# old_IMU.net
KiCad netlist of a schematic drawn in Altium Designer
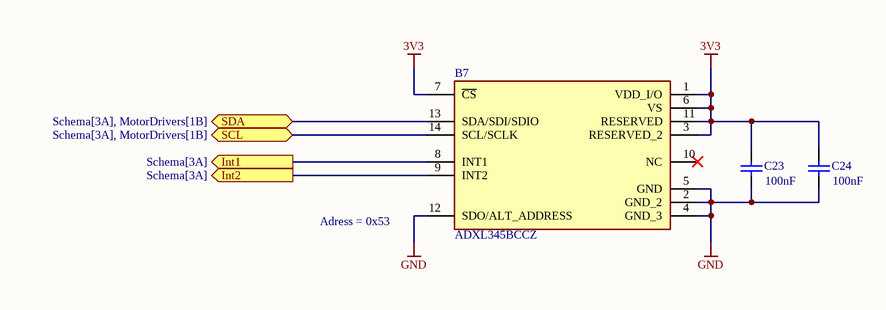
[diagram p0: old_IMU.SchDoc]

(export (version "E")
  (design (tool "Eeschema 10.0.6"))
  (components
    (comp (ref "B7")
      (value "ADXL345BCCZ")
      (footprint "LGA14R80P3X6_300X500X100")
      (description "ADXL345BCCZ, Accelerometer 3-Axis, 0.1  3200 Hz 2  3.6 V, 14-Pin LGA")
      (libsource (lib "SchematicLib") (part "ADXL345BCCZ"))
    )
    (comp (ref "C23")
      (value "100nF")
      (footprint "6-0805_N")
      (description "Capacitor")
      (fields (field (name "Comment") "Cap") (field (name "PUBLISHER") "Altium Limited"))
      (libsource (lib "Miscellaneous Devices") (part "Cap"))
    )
    (comp (ref "C24")
      (value "100nF")
      (footprint "6-0805_N")
      (description "Capacitor")
      (fields (field (name "Comment") "Cap") (field (name "PUBLISHER") "Altium Limited"))
      (libsource (lib "Miscellaneous Devices") (part "Cap"))
    )
  )
  (nets
    (net (code "1") (name "/Int1") (class "Default")
      (node (ref "B7") (pin "8") (pinfunction "INT1_8") (pintype "passive"))
    )
    (net (code "2") (name "/Int2") (class "Default")
      (node (ref "B7") (pin "9") (pinfunction "INT2_9") (pintype "passive"))
    )
    (net (code "3") (name "/SCL") (class "Default")
      (node (ref "B7") (pin "14") (pinfunction "SCL/SCLK_14") (pintype "passive"))
    )
    (net (code "4") (name "/SDA") (class "Default")
      (node (ref "B7") (pin "13") (pinfunction "SDA/SDI/SDIO_13") (pintype "passive"))
    )
    (net (code "5") (name "3V3") (class "Default")
      (node (ref "B7") (pin "1") (pinfunction "VDD_I/O_1") (pintype "passive"))
      (node (ref "B7") (pin "11") (pinfunction "RESERVED_11") (pintype "passive"))
      (node (ref "B7") (pin "3") (pinfunction "RESERVED_2_3") (pintype "passive"))
      (node (ref "B7") (pin "6") (pinfunction "VS_6") (pintype "passive"))
      (node (ref "B7") (pin "7") (pinfunction "~{CS}_7") (pintype "passive"))
      (node (ref "C23") (pin "1") (pinfunction "1_1") (pintype "passive"))
      (node (ref "C24") (pin "1") (pinfunction "1_1") (pintype "passive"))
    )
    (net (code "6") (name "GND") (class "Default")
      (node (ref "B7") (pin "12") (pinfunction "SDO/ALT_ADDRESS_12") (pintype "passive"))
      (node (ref "B7") (pin "2") (pinfunction "GND_2_2") (pintype "passive"))
      (node (ref "B7") (pin "4") (pinfunction "GND_3_4") (pintype "passive"))
      (node (ref "B7") (pin "5") (pinfunction "GND_5") (pintype "passive"))
      (node (ref "C23") (pin "2") (pinfunction "2_2") (pintype "passive"))
      (node (ref "C24") (pin "2") (pinfunction "2_2") (pintype "passive"))
    )
    (net (code "7") (name "unconnected-(B7-NC-Pad10)") (class "Default")
      (node (ref "B7") (pin "10") (pinfunction "NC_10") (pintype "passive+no_connect"))
    )
  )
)
